# 21D_SimpleLoRa_test.net
KiCad netlist of a schematic drawn in Altium Designer
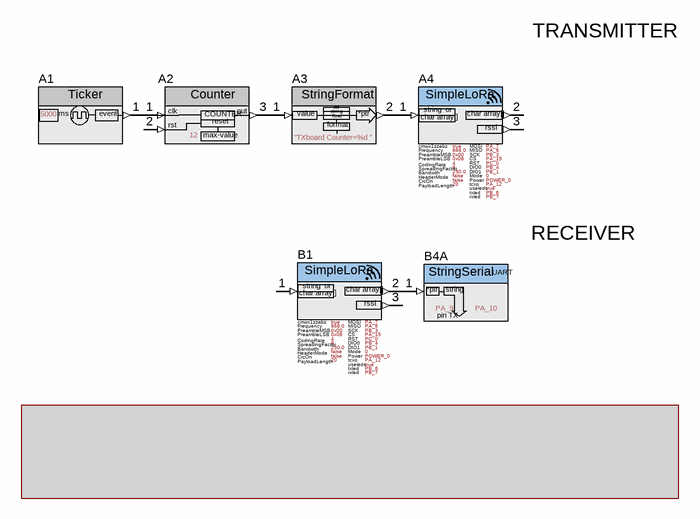
[diagram p0: 21D_SimpleLoRa_test.SchDoc]

(export (version "E")
  (design (tool "Eeschema 10.0.6"))
  (components
    (comp (ref "A1")
      (value "Ticker")
      (description "Creates a Periodical Event")
      (fields (field (name "NBLOCKSPARAMETER1") "5000"))
      (libsource (lib "studio") (part "NODE-TICKER"))
    )
    (comp (ref "A2")
      (value "Counter")
      (description "Ressetable Counter. Returns to zero, when max-value is reached")
      (fields (field (name "NBLOCKSPARAMETER1") "12"))
      (libsource (lib "studio") (part "NODE-COUNTER"))
    )
    (comp (ref "A3")
      (value "StringFormat")
      (fields (field (name "NBLOCKSPARAMETER1") "\"TXboard Counter=%d \""))
      (libsource (lib "studio") (part "NODE-STRINGFORMAT"))
    )
    (comp (ref "A4")
      (value "SimpleLoRa")
      (fields
        (field (name "NBLOCKSPARAMETER21") "true")
        (field (name "NBLOCKSPARAMETER23") "PB_7")
        (field (name "NBLOCKSPARAMETER22") "PB_6")
        (field (name "PARAMETER 23") "rxled")
        (field (name "PARAMETER 22") "txled")
        (field (name "PARAMETER 21") "useleds")
        (field (name "PARAMETER 20") "tcxo")
        (field (name "NBLOCKSPARAMETER20") "PA_12")
        (field (name "NBLOCKSPARAMETER19") "POWER_0")
        (field (name "PARAMETER 19") "Power")
        (field (name "PARAMETER 18") "Mode")
        (field (name "NBLOCKSPARAMETER18") "0")
        (field (name "NBLOCKSPARAMETER17") "PB_1")
        (field (name "NBLOCKSPARAMETER16") "PB_4")
        (field (name "NBLOCKSPARAMETER15") "PC_0")
        (field (name "NBLOCKSPARAMETER14") "PA_15")
        (field (name "NBLOCKSPARAMETER13") "PB_3")
        (field (name "NBLOCKSPARAMETER12") "PA_6")
        (field (name "NBLOCKSPARAMETER11") "PA_7")
        (field (name "PARAMETER 17") "DIO1")
        (field (name "PARAMETER 16") "DIO0")
        (field (name "PARAMETER 15") "RST")
        (field (name "PARAMETER 14") "CS")
        (field (name "PARAMETER 13") "SCK")
        (field (name "PARAMETER 12") "MISO")
        (field (name "PARAMETER 11") "MOSI")
        (field (name "NBLOCKSPARAMETER10") "20")
        (field (name "NBLOCKSPARAMETER9") "false")
        (field (name "NBLOCKSPARAMETER8") "false")
        (field (name "NBLOCKSPARAMETER7") "250.0")
        (field (name "NBLOCKSPARAMETER6") "9")
        (field (name "NBLOCKSPARAMETER5") "4")
        (field (name "NBLOCKSPARAMETER4") "0x08")
        (field (name "NBLOCKSPARAMETER3") "0x00")
        (field (name "NBLOCKSPARAMETER2") "868.0")
        (field (name "NBLOCKSPARAMETER1") "true")
        (field (name "PARAMETER 5") "CodingRate")
        (field (name "PARAMETER 6") "SpreadingFactor")
        (field (name "PARAMETER 7") "Bandwith")
        (field (name "PARAMETER 8") "HeaderMode")
        (field (name "PARAMETER 9") "CrcOn")
        (field (name "PARAMETER 10") "PayloadLength")
        (field (name "PARAMETER 2") "Frequency")
        (field (name "PARAMETER 4") "PreambleLSB")
        (field (name "PARAMETER 3") "PreambleMSB")
        (field (name "PARAMETER 1") "cmwx1zzabz")
      )
      (libsource (lib "studio") (part "NODE-SimpleLoRa"))
    )
    (comp (ref "B1")
      (value "SimpleLoRa")
      (fields
        (field (name "NBLOCKSPARAMETER21") "true")
        (field (name "NBLOCKSPARAMETER23") "PB_7")
        (field (name "NBLOCKSPARAMETER22") "PB_6")
        (field (name "PARAMETER 23") "rxled")
        (field (name "PARAMETER 22") "txled")
        (field (name "PARAMETER 21") "useleds")
        (field (name "PARAMETER 20") "tcxo")
        (field (name "NBLOCKSPARAMETER20") "PA_12")
        (field (name "NBLOCKSPARAMETER19") "POWER_0")
        (field (name "PARAMETER 19") "Power")
        (field (name "PARAMETER 18") "Mode")
        (field (name "NBLOCKSPARAMETER18") "0")
        (field (name "NBLOCKSPARAMETER17") "PB_1")
        (field (name "NBLOCKSPARAMETER16") "PB_4")
        (field (name "NBLOCKSPARAMETER15") "PC_0")
        (field (name "NBLOCKSPARAMETER14") "PA_15")
        (field (name "NBLOCKSPARAMETER13") "PB_3")
        (field (name "NBLOCKSPARAMETER12") "PA_6")
        (field (name "NBLOCKSPARAMETER11") "PA_7")
        (field (name "PARAMETER 17") "DIO1")
        (field (name "PARAMETER 16") "DIO0")
        (field (name "PARAMETER 15") "RST")
        (field (name "PARAMETER 14") "CS")
        (field (name "PARAMETER 13") "SCK")
        (field (name "PARAMETER 12") "MISO")
        (field (name "PARAMETER 11") "MOSI")
        (field (name "NBLOCKSPARAMETER10") "20")
        (field (name "NBLOCKSPARAMETER9") "false")
        (field (name "NBLOCKSPARAMETER8") "false")
        (field (name "NBLOCKSPARAMETER7") "250.0")
        (field (name "NBLOCKSPARAMETER6") "9")
        (field (name "NBLOCKSPARAMETER5") "4")
        (field (name "NBLOCKSPARAMETER4") "0x08")
        (field (name "NBLOCKSPARAMETER3") "0x00")
        (field (name "NBLOCKSPARAMETER2") "868.0")
        (field (name "NBLOCKSPARAMETER1") "true")
        (field (name "PARAMETER 5") "CodingRate")
        (field (name "PARAMETER 6") "SpreadingFactor")
        (field (name "PARAMETER 7") "Bandwith")
        (field (name "PARAMETER 8") "HeaderMode")
        (field (name "PARAMETER 9") "CrcOn")
        (field (name "PARAMETER 10") "PayloadLength")
        (field (name "PARAMETER 2") "Frequency")
        (field (name "PARAMETER 4") "PreambleLSB")
        (field (name "PARAMETER 3") "PreambleMSB")
        (field (name "PARAMETER 1") "cmwx1zzabz")
      )
      (libsource (lib "studio") (part "NODE-SimpleLoRa"))
    )
    (comp (ref "B4")
      (value "StringSerial")
      (fields (field (name "NBLOCKSPARAMETER2") "PA_10") (field (name "NBLOCKSPARAMETER1") "PA_9"))
      (libsource (lib "studio") (part "NODE-STRINGSERIAL-split"))
    )
  )
  (nets
    (net (code "1") (name "Net-(A1-OUT)") (class "Default")
      (node (ref "A1") (pin "1") (pinfunction "OUT_1") (pintype "output"))
      (node (ref "A2") (pin "1") (pinfunction "COUNT-IN_1") (pintype "input"))
    )
    (net (code "2") (name "Net-(A2-OUT)") (class "Default")
      (node (ref "A2") (pin "3") (pinfunction "OUT_3") (pintype "output"))
      (node (ref "A3") (pin "1") (pinfunction "IN_1") (pintype "input"))
    )
    (net (code "3") (name "Net-(A3-OUT)") (class "Default")
      (node (ref "A3") (pin "2") (pinfunction "OUT_2") (pintype "output"))
      (node (ref "A4") (pin "1") (pinfunction "ValueIn_1") (pintype "input"))
    )
    (net (code "4") (name "Net-(B1-payload)") (class "Default")
      (node (ref "B1") (pin "2") (pinfunction "payload_2") (pintype "output"))
      (node (ref "B4") (pin "1") (pinfunction "TX_1") (pintype "input"))
    )
    (net (code "5") (name "unconnected-(A2-RESET-Pad2)") (class "Default")
      (node (ref "A2") (pin "2") (pinfunction "RESET_2") (pintype "input"))
    )
    (net (code "6") (name "unconnected-(A4-payload-Pad2)") (class "Default")
      (node (ref "A4") (pin "2") (pinfunction "payload_2") (pintype "output"))
    )
    (net (code "7") (name "unconnected-(A4-rssi-Pad3)") (class "Default")
      (node (ref "A4") (pin "3") (pinfunction "rssi_3") (pintype "output"))
    )
    (net (code "8") (name "unconnected-(B1-ValueIn-Pad1)") (class "Default")
      (node (ref "B1") (pin "1") (pinfunction "ValueIn_1") (pintype "input"))
    )
    (net (code "9") (name "unconnected-(B1-rssi-Pad3)") (class "Default")
      (node (ref "B1") (pin "3") (pinfunction "rssi_3") (pintype "output"))
    )
  )
)
